# White.net
KiCad netlist of a schematic drawn in EAGLE
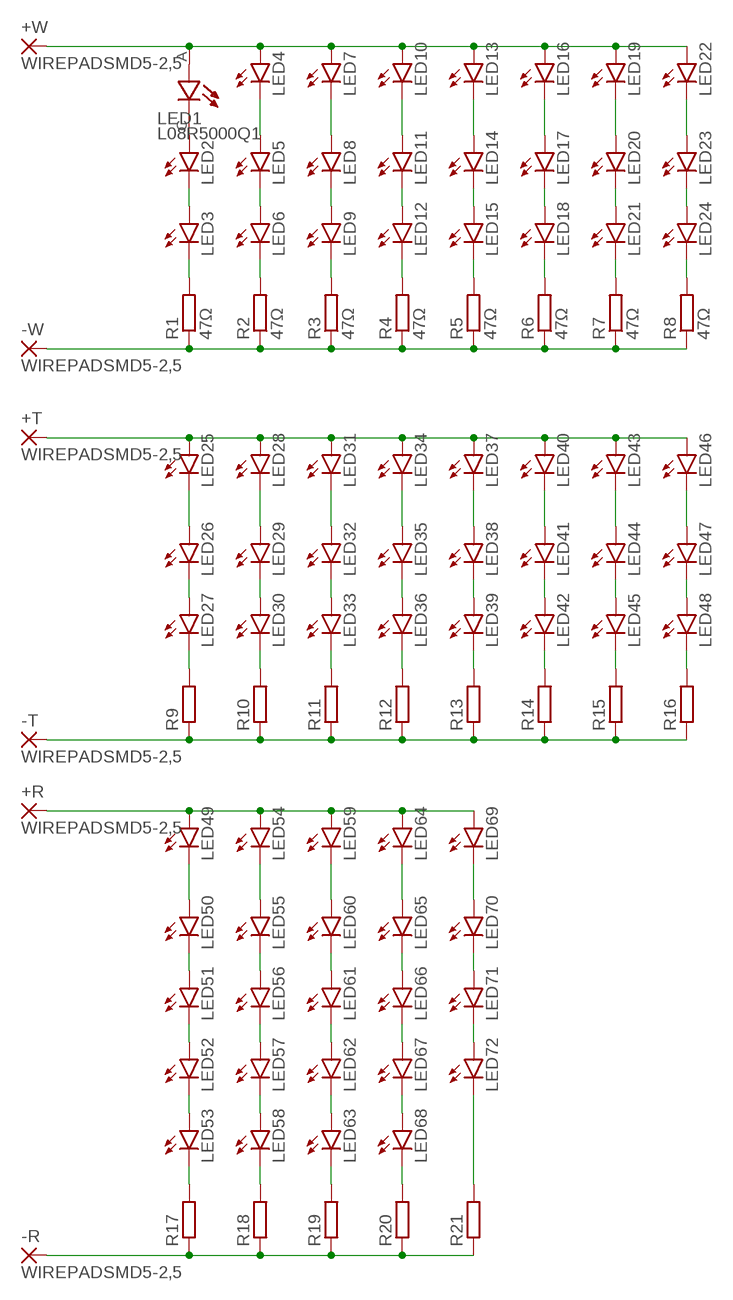
[diagram p0: schematic, sheet 1]

(export (version "E")
  (design (tool "Eeschema 10.0.6"))
  (components
    (comp (ref "+R")
      (value "WIREPADSMD5-2,5")
      (footprint "eagle-import:5-2,5")
      (libsource (lib "eagle-import") (part "WIREPADSMD5-2,5"))
    )
    (comp (ref "+T")
      (value "WIREPADSMD5-2,5")
      (footprint "eagle-import:5-2,5")
      (libsource (lib "eagle-import") (part "WIREPADSMD5-2,5"))
    )
    (comp (ref "+W")
      (value "WIREPADSMD5-2,5")
      (footprint "eagle-import:5-2,5")
      (libsource (lib "eagle-import") (part "WIREPADSMD5-2,5"))
    )
    (comp (ref "-R")
      (value "WIREPADSMD5-2,5")
      (footprint "eagle-import:5-2,5")
      (libsource (lib "eagle-import") (part "WIREPADSMD5-2,5"))
    )
    (comp (ref "-T")
      (value "WIREPADSMD5-2,5")
      (footprint "eagle-import:5-2,5")
      (libsource (lib "eagle-import") (part "WIREPADSMD5-2,5"))
    )
    (comp (ref "-W")
      (value "WIREPADSMD5-2,5")
      (footprint "eagle-import:5-2,5")
      (libsource (lib "eagle-import") (part "WIREPADSMD5-2,5"))
    )
    (comp (ref "LED1")
      (value "L08R5000Q1")
      (footprint "eagle-import:LEDRD254W57D500H1070")
      (fields (field (name "MF") "LED Technology"))
      (libsource (lib "eagle-import") (part "L08R5000Q1"))
    )
    (comp (ref "LED2")
      (value "LED5MM")
      (footprint "eagle-import:LED5MM")
      (libsource (lib "eagle-import") (part "LED5MM"))
    )
    (comp (ref "LED3")
      (value "LED5MM")
      (footprint "eagle-import:LED5MM")
      (libsource (lib "eagle-import") (part "LED5MM"))
    )
    (comp (ref "LED4")
      (value "LED5MM")
      (footprint "eagle-import:LED5MM")
      (libsource (lib "eagle-import") (part "LED5MM"))
    )
    (comp (ref "LED5")
      (value "LED5MM")
      (footprint "eagle-import:LED5MM")
      (libsource (lib "eagle-import") (part "LED5MM"))
    )
    (comp (ref "LED6")
      (value "LED5MM")
      (footprint "eagle-import:LED5MM")
      (libsource (lib "eagle-import") (part "LED5MM"))
    )
    (comp (ref "LED7")
      (value "LED5MM")
      (footprint "eagle-import:LED5MM")
      (libsource (lib "eagle-import") (part "LED5MM"))
    )
    (comp (ref "LED8")
      (value "LED5MM")
      (footprint "eagle-import:LED5MM")
      (libsource (lib "eagle-import") (part "LED5MM"))
    )
    (comp (ref "LED9")
      (value "LED5MM")
      (footprint "eagle-import:LED5MM")
      (libsource (lib "eagle-import") (part "LED5MM"))
    )
    (comp (ref "LED10")
      (value "LED5MM")
      (footprint "eagle-import:LED5MM")
      (libsource (lib "eagle-import") (part "LED5MM"))
    )
    (comp (ref "LED11")
      (value "LED5MM")
      (footprint "eagle-import:LED5MM")
      (libsource (lib "eagle-import") (part "LED5MM"))
    )
    (comp (ref "LED12")
      (value "LED5MM")
      (footprint "eagle-import:LED5MM")
      (libsource (lib "eagle-import") (part "LED5MM"))
    )
    (comp (ref "LED13")
      (value "LED5MM")
      (footprint "eagle-import:LED5MM")
      (libsource (lib "eagle-import") (part "LED5MM"))
    )
    (comp (ref "LED14")
      (value "LED5MM")
      (footprint "eagle-import:LED5MM")
      (libsource (lib "eagle-import") (part "LED5MM"))
    )
    (comp (ref "LED15")
      (value "LED5MM")
      (footprint "eagle-import:LED5MM")
      (libsource (lib "eagle-import") (part "LED5MM"))
    )
    (comp (ref "LED16")
      (value "LED5MM")
      (footprint "eagle-import:LED5MM")
      (libsource (lib "eagle-import") (part "LED5MM"))
    )
    (comp (ref "LED17")
      (value "LED5MM")
      (footprint "eagle-import:LED5MM")
      (libsource (lib "eagle-import") (part "LED5MM"))
    )
    (comp (ref "LED18")
      (value "LED5MM")
      (footprint "eagle-import:LED5MM")
      (libsource (lib "eagle-import") (part "LED5MM"))
    )
    (comp (ref "LED19")
      (value "LED5MM")
      (footprint "eagle-import:LED5MM")
      (libsource (lib "eagle-import") (part "LED5MM"))
    )
    (comp (ref "LED20")
      (value "LED5MM")
      (footprint "eagle-import:LED5MM")
      (libsource (lib "eagle-import") (part "LED5MM"))
    )
    (comp (ref "LED21")
      (value "LED5MM")
      (footprint "eagle-import:LED5MM")
      (libsource (lib "eagle-import") (part "LED5MM"))
    )
    (comp (ref "LED22")
      (value "LED5MM")
      (footprint "eagle-import:LED5MM")
      (libsource (lib "eagle-import") (part "LED5MM"))
    )
    (comp (ref "LED23")
      (value "LED5MM")
      (footprint "eagle-import:LED5MM")
      (libsource (lib "eagle-import") (part "LED5MM"))
    )
    (comp (ref "LED24")
      (value "LED5MM")
      (footprint "eagle-import:LED5MM")
      (libsource (lib "eagle-import") (part "LED5MM"))
    )
    (comp (ref "LED25")
      (value "LED5MM")
      (footprint "eagle-import:LED5MM")
      (libsource (lib "eagle-import") (part "LED5MM"))
    )
    (comp (ref "LED26")
      (value "LED5MM")
      (footprint "eagle-import:LED5MM")
      (libsource (lib "eagle-import") (part "LED5MM"))
    )
    (comp (ref "LED27")
      (value "LED5MM")
      (footprint "eagle-import:LED5MM")
      (libsource (lib "eagle-import") (part "LED5MM"))
    )
    (comp (ref "LED28")
      (value "LED5MM")
      (footprint "eagle-import:LED5MM")
      (libsource (lib "eagle-import") (part "LED5MM"))
    )
    (comp (ref "LED29")
      (value "LED5MM")
      (footprint "eagle-import:LED5MM")
      (libsource (lib "eagle-import") (part "LED5MM"))
    )
    (comp (ref "LED30")
      (value "LED5MM")
      (footprint "eagle-import:LED5MM")
      (libsource (lib "eagle-import") (part "LED5MM"))
    )
    (comp (ref "LED31")
      (value "LED5MM")
      (footprint "eagle-import:LED5MM")
      (libsource (lib "eagle-import") (part "LED5MM"))
    )
    (comp (ref "LED32")
      (value "LED5MM")
      (footprint "eagle-import:LED5MM")
      (libsource (lib "eagle-import") (part "LED5MM"))
    )
    (comp (ref "LED33")
      (value "LED5MM")
      (footprint "eagle-import:LED5MM")
      (libsource (lib "eagle-import") (part "LED5MM"))
    )
    (comp (ref "LED34")
      (value "LED5MM")
      (footprint "eagle-import:LED5MM")
      (libsource (lib "eagle-import") (part "LED5MM"))
    )
    (comp (ref "LED35")
      (value "LED5MM")
      (footprint "eagle-import:LED5MM")
      (libsource (lib "eagle-import") (part "LED5MM"))
    )
    (comp (ref "LED36")
      (value "LED5MM")
      (footprint "eagle-import:LED5MM")
      (libsource (lib "eagle-import") (part "LED5MM"))
    )
    (comp (ref "LED37")
      (value "LED5MM")
      (footprint "eagle-import:LED5MM")
      (libsource (lib "eagle-import") (part "LED5MM"))
    )
    (comp (ref "LED38")
      (value "LED5MM")
      (footprint "eagle-import:LED5MM")
      (libsource (lib "eagle-import") (part "LED5MM"))
    )
    (comp (ref "LED39")
      (value "LED5MM")
      (footprint "eagle-import:LED5MM")
      (libsource (lib "eagle-import") (part "LED5MM"))
    )
    (comp (ref "LED40")
      (value "LED5MM")
      (footprint "eagle-import:LED5MM")
      (libsource (lib "eagle-import") (part "LED5MM"))
    )
    (comp (ref "LED41")
      (value "LED5MM")
      (footprint "eagle-import:LED5MM")
      (libsource (lib "eagle-import") (part "LED5MM"))
    )
    (comp (ref "LED42")
      (value "LED5MM")
      (footprint "eagle-import:LED5MM")
      (libsource (lib "eagle-import") (part "LED5MM"))
    )
    (comp (ref "LED43")
      (value "LED5MM")
      (footprint "eagle-import:LED5MM")
      (libsource (lib "eagle-import") (part "LED5MM"))
    )
    (comp (ref "LED44")
      (value "LED5MM")
      (footprint "eagle-import:LED5MM")
      (libsource (lib "eagle-import") (part "LED5MM"))
    )
    (comp (ref "LED45")
      (value "LED5MM")
      (footprint "eagle-import:LED5MM")
      (libsource (lib "eagle-import") (part "LED5MM"))
    )
    (comp (ref "LED46")
      (value "LED5MM")
      (footprint "eagle-import:LED5MM")
      (libsource (lib "eagle-import") (part "LED5MM"))
    )
    (comp (ref "LED47")
      (value "LED5MM")
      (footprint "eagle-import:LED5MM")
      (libsource (lib "eagle-import") (part "LED5MM"))
    )
    (comp (ref "LED48")
      (value "LED5MM")
      (footprint "eagle-import:LED5MM")
      (libsource (lib "eagle-import") (part "LED5MM"))
    )
    (comp (ref "LED49")
      (value "LED5MM")
      (footprint "eagle-import:LED5MM")
      (libsource (lib "eagle-import") (part "LED5MM"))
    )
    (comp (ref "LED50")
      (value "LED5MM")
      (footprint "eagle-import:LED5MM")
      (libsource (lib "eagle-import") (part "LED5MM"))
    )
    (comp (ref "LED51")
      (value "LED5MM")
      (footprint "eagle-import:LED5MM")
      (libsource (lib "eagle-import") (part "LED5MM"))
    )
    (comp (ref "LED52")
      (value "LED5MM")
      (footprint "eagle-import:LED5MM")
      (libsource (lib "eagle-import") (part "LED5MM"))
    )
    (comp (ref "LED53")
      (value "LED5MM")
      (footprint "eagle-import:LED5MM")
      (libsource (lib "eagle-import") (part "LED5MM"))
    )
    (comp (ref "LED54")
      (value "LED5MM")
      (footprint "eagle-import:LED5MM")
      (libsource (lib "eagle-import") (part "LED5MM"))
    )
    (comp (ref "LED55")
      (value "LED5MM")
      (footprint "eagle-import:LED5MM")
      (libsource (lib "eagle-import") (part "LED5MM"))
    )
    (comp (ref "LED56")
      (value "LED5MM")
      (footprint "eagle-import:LED5MM")
      (libsource (lib "eagle-import") (part "LED5MM"))
    )
    (comp (ref "LED57")
      (value "LED5MM")
      (footprint "eagle-import:LED5MM")
      (libsource (lib "eagle-import") (part "LED5MM"))
    )
    (comp (ref "LED58")
      (value "LED5MM")
      (footprint "eagle-import:LED5MM")
      (libsource (lib "eagle-import") (part "LED5MM"))
    )
    (comp (ref "LED59")
      (value "LED5MM")
      (footprint "eagle-import:LED5MM")
      (libsource (lib "eagle-import") (part "LED5MM"))
    )
    (comp (ref "LED60")
      (value "LED5MM")
      (footprint "eagle-import:LED5MM")
      (libsource (lib "eagle-import") (part "LED5MM"))
    )
    (comp (ref "LED61")
      (value "LED5MM")
      (footprint "eagle-import:LED5MM")
      (libsource (lib "eagle-import") (part "LED5MM"))
    )
    (comp (ref "LED62")
      (value "LED5MM")
      (footprint "eagle-import:LED5MM")
      (libsource (lib "eagle-import") (part "LED5MM"))
    )
    (comp (ref "LED63")
      (value "LED5MM")
      (footprint "eagle-import:LED5MM")
      (libsource (lib "eagle-import") (part "LED5MM"))
    )
    (comp (ref "LED64")
      (value "LED5MM")
      (footprint "eagle-import:LED5MM")
      (libsource (lib "eagle-import") (part "LED5MM"))
    )
    (comp (ref "LED65")
      (value "LED5MM")
      (footprint "eagle-import:LED5MM")
      (libsource (lib "eagle-import") (part "LED5MM"))
    )
    (comp (ref "LED66")
      (value "LED5MM")
      (footprint "eagle-import:LED5MM")
      (libsource (lib "eagle-import") (part "LED5MM"))
    )
    (comp (ref "LED67")
      (value "LED5MM")
      (footprint "eagle-import:LED5MM")
      (libsource (lib "eagle-import") (part "LED5MM"))
    )
    (comp (ref "LED68")
      (value "LED5MM")
      (footprint "eagle-import:LED5MM")
      (libsource (lib "eagle-import") (part "LED5MM"))
    )
    (comp (ref "LED69")
      (value "LED5MM")
      (footprint "eagle-import:LED5MM")
      (libsource (lib "eagle-import") (part "LED5MM"))
    )
    (comp (ref "LED70")
      (value "LED5MM")
      (footprint "eagle-import:LED5MM")
      (libsource (lib "eagle-import") (part "LED5MM"))
    )
    (comp (ref "LED71")
      (value "LED5MM")
      (footprint "eagle-import:LED5MM")
      (libsource (lib "eagle-import") (part "LED5MM"))
    )
    (comp (ref "LED72")
      (value "LED5MM")
      (footprint "eagle-import:LED5MM")
      (libsource (lib "eagle-import") (part "LED5MM"))
    )
    (comp (ref "R1")
      (value "47Ω")
      (footprint "eagle-import:0411_15")
      (libsource (lib "eagle-import") (part "R-EU_0411/15"))
    )
    (comp (ref "R2")
      (value "47Ω")
      (footprint "eagle-import:0411_15")
      (libsource (lib "eagle-import") (part "R-EU_0411/15"))
    )
    (comp (ref "R3")
      (value "47Ω")
      (footprint "eagle-import:0411_15")
      (libsource (lib "eagle-import") (part "R-EU_0411/15"))
    )
    (comp (ref "R4")
      (value "47Ω")
      (footprint "eagle-import:0411_15")
      (libsource (lib "eagle-import") (part "R-EU_0411/15"))
    )
    (comp (ref "R5")
      (value "47Ω")
      (footprint "eagle-import:0411_15")
      (libsource (lib "eagle-import") (part "R-EU_0411/15"))
    )
    (comp (ref "R6")
      (value "47Ω")
      (footprint "eagle-import:0411_15")
      (libsource (lib "eagle-import") (part "R-EU_0411/15"))
    )
    (comp (ref "R7")
      (value "47Ω")
      (footprint "eagle-import:0411_15")
      (libsource (lib "eagle-import") (part "R-EU_0411/15"))
    )
    (comp (ref "R8")
      (value "47Ω")
      (footprint "eagle-import:0411_15")
      (libsource (lib "eagle-import") (part "R-EU_0411/15"))
    )
    (comp (ref "R9")
      (value "R-EU_0207/12")
      (footprint "eagle-import:0207_12")
      (libsource (lib "eagle-import") (part "R-EU_0207/12"))
    )
    (comp (ref "R10")
      (value "R-EU_0207/12")
      (footprint "eagle-import:0207_12")
      (libsource (lib "eagle-import") (part "R-EU_0207/12"))
    )
    (comp (ref "R11")
      (value "R-EU_0207/12")
      (footprint "eagle-import:0207_12")
      (libsource (lib "eagle-import") (part "R-EU_0207/12"))
    )
    (comp (ref "R12")
      (value "R-EU_0207/12")
      (footprint "eagle-import:0207_12")
      (libsource (lib "eagle-import") (part "R-EU_0207/12"))
    )
    (comp (ref "R13")
      (value "R-EU_0207/12")
      (footprint "eagle-import:0207_12")
      (libsource (lib "eagle-import") (part "R-EU_0207/12"))
    )
    (comp (ref "R14")
      (value "R-EU_0207/12")
      (footprint "eagle-import:0207_12")
      (libsource (lib "eagle-import") (part "R-EU_0207/12"))
    )
    (comp (ref "R15")
      (value "R-EU_0207/12")
      (footprint "eagle-import:0207_12")
      (libsource (lib "eagle-import") (part "R-EU_0207/12"))
    )
    (comp (ref "R16")
      (value "R-EU_0207/12")
      (footprint "eagle-import:0207_12")
      (libsource (lib "eagle-import") (part "R-EU_0207/12"))
    )
    (comp (ref "R17")
      (value "R-EU_0207/12")
      (footprint "eagle-import:0207_12")
      (libsource (lib "eagle-import") (part "R-EU_0207/12"))
    )
    (comp (ref "R18")
      (value "R-EU_0207/12")
      (footprint "eagle-import:0207_12")
      (libsource (lib "eagle-import") (part "R-EU_0207/12"))
    )
    (comp (ref "R19")
      (value "R-EU_0207/12")
      (footprint "eagle-import:0207_12")
      (libsource (lib "eagle-import") (part "R-EU_0207/12"))
    )
    (comp (ref "R20")
      (value "R-EU_0207/12")
      (footprint "eagle-import:0207_12")
      (libsource (lib "eagle-import") (part "R-EU_0207/12"))
    )
    (comp (ref "R21")
      (value "R-EU_0207/12")
      (footprint "eagle-import:0207_12")
      (libsource (lib "eagle-import") (part "R-EU_0207/12"))
    )
  )
  (nets
    (net (code "1") (name "Net-(+R-P)") (class "Default")
      (node (ref "+R") (pin "1") (pinfunction "P_1") (pintype "passive"))
      (node (ref "LED49") (pin "A") (pinfunction "A_A") (pintype "passive"))
      (node (ref "LED54") (pin "A") (pinfunction "A_A") (pintype "passive"))
      (node (ref "LED59") (pin "A") (pinfunction "A_A") (pintype "passive"))
      (node (ref "LED64") (pin "A") (pinfunction "A_A") (pintype "passive"))
      (node (ref "LED69") (pin "A") (pinfunction "A_A") (pintype "passive"))
    )
    (net (code "2") (name "Net-(+T-P)") (class "Default")
      (node (ref "+T") (pin "1") (pinfunction "P_1") (pintype "passive"))
      (node (ref "LED25") (pin "A") (pinfunction "A_A") (pintype "passive"))
      (node (ref "LED28") (pin "A") (pinfunction "A_A") (pintype "passive"))
      (node (ref "LED31") (pin "A") (pinfunction "A_A") (pintype "passive"))
      (node (ref "LED34") (pin "A") (pinfunction "A_A") (pintype "passive"))
      (node (ref "LED37") (pin "A") (pinfunction "A_A") (pintype "passive"))
      (node (ref "LED40") (pin "A") (pinfunction "A_A") (pintype "passive"))
      (node (ref "LED43") (pin "A") (pinfunction "A_A") (pintype "passive"))
      (node (ref "LED46") (pin "A") (pinfunction "A_A") (pintype "passive"))
    )
    (net (code "3") (name "Net-(+W-P)") (class "Default")
      (node (ref "+W") (pin "1") (pinfunction "P_1") (pintype "passive"))
      (node (ref "LED1") (pin "A") (pinfunction "A_A") (pintype "passive"))
      (node (ref "LED10") (pin "A") (pinfunction "A_A") (pintype "passive"))
      (node (ref "LED13") (pin "A") (pinfunction "A_A") (pintype "passive"))
      (node (ref "LED16") (pin "A") (pinfunction "A_A") (pintype "passive"))
      (node (ref "LED19") (pin "A") (pinfunction "A_A") (pintype "passive"))
      (node (ref "LED22") (pin "A") (pinfunction "A_A") (pintype "passive"))
      (node (ref "LED4") (pin "A") (pinfunction "A_A") (pintype "passive"))
      (node (ref "LED7") (pin "A") (pinfunction "A_A") (pintype "passive"))
    )
    (net (code "4") (name "Net-(-R-P)") (class "Default")
      (node (ref "-R") (pin "1") (pinfunction "P_1") (pintype "passive"))
      (node (ref "R17") (pin "1") (pinfunction "1_1") (pintype "passive"))
      (node (ref "R18") (pin "1") (pinfunction "1_1") (pintype "passive"))
      (node (ref "R19") (pin "1") (pinfunction "1_1") (pintype "passive"))
      (node (ref "R20") (pin "1") (pinfunction "1_1") (pintype "passive"))
      (node (ref "R21") (pin "1") (pinfunction "1_1") (pintype "passive"))
    )
    (net (code "5") (name "Net-(-T-P)") (class "Default")
      (node (ref "-T") (pin "1") (pinfunction "P_1") (pintype "passive"))
      (node (ref "R10") (pin "1") (pinfunction "1_1") (pintype "passive"))
      (node (ref "R11") (pin "1") (pinfunction "1_1") (pintype "passive"))
      (node (ref "R12") (pin "1") (pinfunction "1_1") (pintype "passive"))
      (node (ref "R13") (pin "1") (pinfunction "1_1") (pintype "passive"))
      (node (ref "R14") (pin "1") (pinfunction "1_1") (pintype "passive"))
      (node (ref "R15") (pin "1") (pinfunction "1_1") (pintype "passive"))
      (node (ref "R16") (pin "1") (pinfunction "1_1") (pintype "passive"))
      (node (ref "R9") (pin "1") (pinfunction "1_1") (pintype "passive"))
    )
    (net (code "6") (name "Net-(-W-P)") (class "Default")
      (node (ref "-W") (pin "1") (pinfunction "P_1") (pintype "passive"))
      (node (ref "R1") (pin "1") (pinfunction "1_1") (pintype "passive"))
      (node (ref "R2") (pin "1") (pinfunction "1_1") (pintype "passive"))
      (node (ref "R3") (pin "1") (pinfunction "1_1") (pintype "passive"))
      (node (ref "R4") (pin "1") (pinfunction "1_1") (pintype "passive"))
      (node (ref "R5") (pin "1") (pinfunction "1_1") (pintype "passive"))
      (node (ref "R6") (pin "1") (pinfunction "1_1") (pintype "passive"))
      (node (ref "R7") (pin "1") (pinfunction "1_1") (pintype "passive"))
      (node (ref "R8") (pin "1") (pinfunction "1_1") (pintype "passive"))
    )
    (net (code "7") (name "Net-(LED1-PadC)") (class "Default")
      (node (ref "LED1") (pin "C") (pinfunction "C_C") (pintype "passive"))
      (node (ref "LED2") (pin "A") (pinfunction "A_A") (pintype "passive"))
    )
    (net (code "8") (name "Net-(LED2-C)") (class "Default")
      (node (ref "LED2") (pin "K") (pinfunction "C_K") (pintype "passive"))
      (node (ref "LED3") (pin "A") (pinfunction "A_A") (pintype "passive"))
    )
    (net (code "9") (name "Net-(LED3-C)") (class "Default")
      (node (ref "LED3") (pin "K") (pinfunction "C_K") (pintype "passive"))
      (node (ref "R1") (pin "2") (pinfunction "2_2") (pintype "passive"))
    )
    (net (code "10") (name "Net-(LED4-C)") (class "Default")
      (node (ref "LED4") (pin "K") (pinfunction "C_K") (pintype "passive"))
      (node (ref "LED5") (pin "A") (pinfunction "A_A") (pintype "passive"))
    )
    (net (code "11") (name "Net-(LED5-C)") (class "Default")
      (node (ref "LED5") (pin "K") (pinfunction "C_K") (pintype "passive"))
      (node (ref "LED6") (pin "A") (pinfunction "A_A") (pintype "passive"))
    )
    (net (code "12") (name "Net-(LED6-C)") (class "Default")
      (node (ref "LED6") (pin "K") (pinfunction "C_K") (pintype "passive"))
      (node (ref "R2") (pin "2") (pinfunction "2_2") (pintype "passive"))
    )
    (net (code "13") (name "Net-(LED7-C)") (class "Default")
      (node (ref "LED7") (pin "K") (pinfunction "C_K") (pintype "passive"))
      (node (ref "LED8") (pin "A") (pinfunction "A_A") (pintype "passive"))
    )
    (net (code "14") (name "Net-(LED8-C)") (class "Default")
      (node (ref "LED8") (pin "K") (pinfunction "C_K") (pintype "passive"))
      (node (ref "LED9") (pin "A") (pinfunction "A_A") (pintype "passive"))
    )
    (net (code "15") (name "Net-(LED9-C)") (class "Default")
      (node (ref "LED9") (pin "K") (pinfunction "C_K") (pintype "passive"))
      (node (ref "R3") (pin "2") (pinfunction "2_2") (pintype "passive"))
    )
    (net (code "16") (name "Net-(LED10-C)") (class "Default")
      (node (ref "LED10") (pin "K") (pinfunction "C_K") (pintype "passive"))
      (node (ref "LED11") (pin "A") (pinfunction "A_A") (pintype "passive"))
    )
    (net (code "17") (name "Net-(LED11-C)") (class "Default")
      (node (ref "LED11") (pin "K") (pinfunction "C_K") (pintype "passive"))
      (node (ref "LED12") (pin "A") (pinfunction "A_A") (pintype "passive"))
    )
    (net (code "18") (name "Net-(LED12-C)") (class "Default")
      (node (ref "LED12") (pin "K") (pinfunction "C_K") (pintype "passive"))
      (node (ref "R4") (pin "2") (pinfunction "2_2") (pintype "passive"))
    )
    (net (code "19") (name "Net-(LED13-C)") (class "Default")
      (node (ref "LED13") (pin "K") (pinfunction "C_K") (pintype "passive"))
      (node (ref "LED14") (pin "A") (pinfunction "A_A") (pintype "passive"))
    )
    (net (code "20") (name "Net-(LED14-C)") (class "Default")
      (node (ref "LED14") (pin "K") (pinfunction "C_K") (pintype "passive"))
      (node (ref "LED15") (pin "A") (pinfunction "A_A") (pintype "passive"))
    )
    (net (code "21") (name "Net-(LED15-C)") (class "Default")
      (node (ref "LED15") (pin "K") (pinfunction "C_K") (pintype "passive"))
      (node (ref "R5") (pin "2") (pinfunction "2_2") (pintype "passive"))
    )
    (net (code "22") (name "Net-(LED16-C)") (class "Default")
      (node (ref "LED16") (pin "K") (pinfunction "C_K") (pintype "passive"))
      (node (ref "LED17") (pin "A") (pinfunction "A_A") (pintype "passive"))
    )
    (net (code "23") (name "Net-(LED17-C)") (class "Default")
      (node (ref "LED17") (pin "K") (pinfunction "C_K") (pintype "passive"))
      (node (ref "LED18") (pin "A") (pinfunction "A_A") (pintype "passive"))
    )
    (net (code "24") (name "Net-(LED18-C)") (class "Default")
      (node (ref "LED18") (pin "K") (pinfunction "C_K") (pintype "passive"))
      (node (ref "R6") (pin "2") (pinfunction "2_2") (pintype "passive"))
    )
    (net (code "25") (name "Net-(LED19-C)") (class "Default")
      (node (ref "LED19") (pin "K") (pinfunction "C_K") (pintype "passive"))
      (node (ref "LED20") (pin "A") (pinfunction "A_A") (pintype "passive"))
    )
    (net (code "26") (name "Net-(LED20-C)") (class "Default")
      (node (ref "LED20") (pin "K") (pinfunction "C_K") (pintype "passive"))
      (node (ref "LED21") (pin "A") (pinfunction "A_A") (pintype "passive"))
    )
    (net (code "27") (name "Net-(LED21-C)") (class "Default")
      (node (ref "LED21") (pin "K") (pinfunction "C_K") (pintype "passive"))
      (node (ref "R7") (pin "2") (pinfunction "2_2") (pintype "passive"))
    )
    (net (code "28") (name "Net-(LED22-C)") (class "Default")
      (node (ref "LED22") (pin "K") (pinfunction "C_K") (pintype "passive"))
      (node (ref "LED23") (pin "A") (pinfunction "A_A") (pintype "passive"))
    )
    (net (code "29") (name "Net-(LED23-C)") (class "Default")
      (node (ref "LED23") (pin "K") (pinfunction "C_K") (pintype "passive"))
      (node (ref "LED24") (pin "A") (pinfunction "A_A") (pintype "passive"))
    )
    (net (code "30") (name "Net-(LED24-C)") (class "Default")
      (node (ref "LED24") (pin "K") (pinfunction "C_K") (pintype "passive"))
      (node (ref "R8") (pin "2") (pinfunction "2_2") (pintype "passive"))
    )
    (net (code "31") (name "Net-(LED25-C)") (class "Default")
      (node (ref "LED25") (pin "K") (pinfunction "C_K") (pintype "passive"))
      (node (ref "LED26") (pin "A") (pinfunction "A_A") (pintype "passive"))
    )
    (net (code "32") (name "Net-(LED26-C)") (class "Default")
      (node (ref "LED26") (pin "K") (pinfunction "C_K") (pintype "passive"))
      (node (ref "LED27") (pin "A") (pinfunction "A_A") (pintype "passive"))
    )
    (net (code "33") (name "Net-(LED27-C)") (class "Default")
      (node (ref "LED27") (pin "K") (pinfunction "C_K") (pintype "passive"))
      (node (ref "R9") (pin "2") (pinfunction "2_2") (pintype "passive"))
    )
    (net (code "34") (name "Net-(LED28-C)") (class "Default")
      (node (ref "LED28") (pin "K") (pinfunction "C_K") (pintype "passive"))
      (node (ref "LED29") (pin "A") (pinfunction "A_A") (pintype "passive"))
    )
    (net (code "35") (name "Net-(LED29-C)") (class "Default")
      (node (ref "LED29") (pin "K") (pinfunction "C_K") (pintype "passive"))
      (node (ref "LED30") (pin "A") (pinfunction "A_A") (pintype "passive"))
    )
    (net (code "36") (name "Net-(LED30-C)") (class "Default")
      (node (ref "LED30") (pin "K") (pinfunction "C_K") (pintype "passive"))
      (node (ref "R10") (pin "2") (pinfunction "2_2") (pintype "passive"))
    )
    (net (code "37") (name "Net-(LED31-C)") (class "Default")
      (node (ref "LED31") (pin "K") (pinfunction "C_K") (pintype "passive"))
      (node (ref "LED32") (pin "A") (pinfunction "A_A") (pintype "passive"))
    )
    (net (code "38") (name "Net-(LED32-C)") (class "Default")
      (node (ref "LED32") (pin "K") (pinfunction "C_K") (pintype "passive"))
      (node (ref "LED33") (pin "A") (pinfunction "A_A") (pintype "passive"))
    )
    (net (code "39") (name "Net-(LED33-C)") (class "Default")
      (node (ref "LED33") (pin "K") (pinfunction "C_K") (pintype "passive"))
      (node (ref "R11") (pin "2") (pinfunction "2_2") (pintype "passive"))
    )
    (net (code "40") (name "Net-(LED34-C)") (class "Default")
      (node (ref "LED34") (pin "K") (pinfunction "C_K") (pintype "passive"))
      (node (ref "LED35") (pin "A") (pinfunction "A_A") (pintype "passive"))
    )
    (net (code "41") (name "Net-(LED35-C)") (class "Default")
      (node (ref "LED35") (pin "K") (pinfunction "C_K") (pintype "passive"))
      (node (ref "LED36") (pin "A") (pinfunction "A_A") (pintype "passive"))
    )
    (net (code "42") (name "Net-(LED36-C)") (class "Default")
      (node (ref "LED36") (pin "K") (pinfunction "C_K") (pintype "passive"))
      (node (ref "R12") (pin "2") (pinfunction "2_2") (pintype "passive"))
    )
    (net (code "43") (name "Net-(LED37-C)") (class "Default")
      (node (ref "LED37") (pin "K") (pinfunction "C_K") (pintype "passive"))
      (node (ref "LED38") (pin "A") (pinfunction "A_A") (pintype "passive"))
    )
    (net (code "44") (name "Net-(LED38-C)") (class "Default")
      (node (ref "LED38") (pin "K") (pinfunction "C_K") (pintype "passive"))
      (node (ref "LED39") (pin "A") (pinfunction "A_A") (pintype "passive"))
    )
    (net (code "45") (name "Net-(LED39-C)") (class "Default")
      (node (ref "LED39") (pin "K") (pinfunction "C_K") (pintype "passive"))
      (node (ref "R13") (pin "2") (pinfunction "2_2") (pintype "passive"))
    )
    (net (code "46") (name "Net-(LED40-C)") (class "Default")
      (node (ref "LED40") (pin "K") (pinfunction "C_K") (pintype "passive"))
      (node (ref "LED41") (pin "A") (pinfunction "A_A") (pintype "passive"))
    )
    (net (code "47") (name "Net-(LED41-C)") (class "Default")
      (node (ref "LED41") (pin "K") (pinfunction "C_K") (pintype "passive"))
      (node (ref "LED42") (pin "A") (pinfunction "A_A") (pintype "passive"))
    )
    (net (code "48") (name "Net-(LED42-C)") (class "Default")
      (node (ref "LED42") (pin "K") (pinfunction "C_K") (pintype "passive"))
      (node (ref "R14") (pin "2") (pinfunction "2_2") (pintype "passive"))
    )
    (net (code "49") (name "Net-(LED43-C)") (class "Default")
      (node (ref "LED43") (pin "K") (pinfunction "C_K") (pintype "passive"))
      (node (ref "LED44") (pin "A") (pinfunction "A_A") (pintype "passive"))
    )
    (net (code "50") (name "Net-(LED44-C)") (class "Default")
      (node (ref "LED44") (pin "K") (pinfunction "C_K") (pintype "passive"))
      (node (ref "LED45") (pin "A") (pinfunction "A_A") (pintype "passive"))
    )
    (net (code "51") (name "Net-(LED45-C)") (class "Default")
      (node (ref "LED45") (pin "K") (pinfunction "C_K") (pintype "passive"))
      (node (ref "R15") (pin "2") (pinfunction "2_2") (pintype "passive"))
    )
    (net (code "52") (name "Net-(LED46-C)") (class "Default")
      (node (ref "LED46") (pin "K") (pinfunction "C_K") (pintype "passive"))
      (node (ref "LED47") (pin "A") (pinfunction "A_A") (pintype "passive"))
    )
    (net (code "53") (name "Net-(LED47-C)") (class "Default")
      (node (ref "LED47") (pin "K") (pinfunction "C_K") (pintype "passive"))
      (node (ref "LED48") (pin "A") (pinfunction "A_A") (pintype "passive"))
    )
    (net (code "54") (name "Net-(LED48-C)") (class "Default")
      (node (ref "LED48") (pin "K") (pinfunction "C_K") (pintype "passive"))
      (node (ref "R16") (pin "2") (pinfunction "2_2") (pintype "passive"))
    )
    (net (code "55") (name "Net-(LED49-C)") (class "Default")
      (node (ref "LED49") (pin "K") (pinfunction "C_K") (pintype "passive"))
      (node (ref "LED50") (pin "A") (pinfunction "A_A") (pintype "passive"))
    )
    (net (code "56") (name "Net-(LED50-C)") (class "Default")
      (node (ref "LED50") (pin "K") (pinfunction "C_K") (pintype "passive"))
      (node (ref "LED51") (pin "A") (pinfunction "A_A") (pintype "passive"))
    )
    (net (code "57") (name "Net-(LED51-C)") (class "Default")
      (node (ref "LED51") (pin "K") (pinfunction "C_K") (pintype "passive"))
      (node (ref "LED52") (pin "A") (pinfunction "A_A") (pintype "passive"))
    )
    (net (code "58") (name "Net-(LED52-C)") (class "Default")
      (node (ref "LED52") (pin "K") (pinfunction "C_K") (pintype "passive"))
      (node (ref "LED53") (pin "A") (pinfunction "A_A") (pintype "passive"))
    )
    (net (code "59") (name "Net-(LED53-C)") (class "Default")
      (node (ref "LED53") (pin "K") (pinfunction "C_K") (pintype "passive"))
      (node (ref "R17") (pin "2") (pinfunction "2_2") (pintype "passive"))
    )
    (net (code "60") (name "Net-(LED54-C)") (class "Default")
      (node (ref "LED54") (pin "K") (pinfunction "C_K") (pintype "passive"))
      (node (ref "LED55") (pin "A") (pinfunction "A_A") (pintype "passive"))
    )
    (net (code "61") (name "Net-(LED55-C)") (class "Default")
      (node (ref "LED55") (pin "K") (pinfunction "C_K") (pintype "passive"))
      (node (ref "LED56") (pin "A") (pinfunction "A_A") (pintype "passive"))
    )
    (net (code "62") (name "Net-(LED56-C)") (class "Default")
      (node (ref "LED56") (pin "K") (pinfunction "C_K") (pintype "passive"))
      (node (ref "LED57") (pin "A") (pinfunction "A_A") (pintype "passive"))
    )
    (net (code "63") (name "Net-(LED57-C)") (class "Default")
      (node (ref "LED57") (pin "K") (pinfunction "C_K") (pintype "passive"))
      (node (ref "LED58") (pin "A") (pinfunction "A_A") (pintype "passive"))
    )
    (net (code "64") (name "Net-(LED58-C)") (class "Default")
      (node (ref "LED58") (pin "K") (pinfunction "C_K") (pintype "passive"))
      (node (ref "R18") (pin "2") (pinfunction "2_2") (pintype "passive"))
    )
    (net (code "65") (name "Net-(LED59-C)") (class "Default")
      (node (ref "LED59") (pin "K") (pinfunction "C_K") (pintype "passive"))
      (node (ref "LED60") (pin "A") (pinfunction "A_A") (pintype "passive"))
    )
    (net (code "66") (name "Net-(LED60-C)") (class "Default")
      (node (ref "LED60") (pin "K") (pinfunction "C_K") (pintype "passive"))
      (node (ref "LED61") (pin "A") (pinfunction "A_A") (pintype "passive"))
    )
    (net (code "67") (name "Net-(LED61-C)") (class "Default")
      (node (ref "LED61") (pin "K") (pinfunction "C_K") (pintype "passive"))
      (node (ref "LED62") (pin "A") (pinfunction "A_A") (pintype "passive"))
    )
    (net (code "68") (name "Net-(LED62-C)") (class "Default")
      (node (ref "LED62") (pin "K") (pinfunction "C_K") (pintype "passive"))
      (node (ref "LED63") (pin "A") (pinfunction "A_A") (pintype "passive"))
    )
    (net (code "69") (name "Net-(LED63-C)") (class "Default")
      (node (ref "LED63") (pin "K") (pinfunction "C_K") (pintype "passive"))
      (node (ref "R19") (pin "2") (pinfunction "2_2") (pintype "passive"))
    )
    (net (code "70") (name "Net-(LED64-C)") (class "Default")
      (node (ref "LED64") (pin "K") (pinfunction "C_K") (pintype "passive"))
      (node (ref "LED65") (pin "A") (pinfunction "A_A") (pintype "passive"))
    )
    (net (code "71") (name "Net-(LED65-C)") (class "Default")
      (node (ref "LED65") (pin "K") (pinfunction "C_K") (pintype "passive"))
      (node (ref "LED66") (pin "A") (pinfunction "A_A") (pintype "passive"))
    )
    (net (code "72") (name "Net-(LED66-C)") (class "Default")
      (node (ref "LED66") (pin "K") (pinfunction "C_K") (pintype "passive"))
      (node (ref "LED67") (pin "A") (pinfunction "A_A") (pintype "passive"))
    )
    (net (code "73") (name "Net-(LED67-C)") (class "Default")
      (node (ref "LED67") (pin "K") (pinfunction "C_K") (pintype "passive"))
      (node (ref "LED68") (pin "A") (pinfunction "A_A") (pintype "passive"))
    )
    (net (code "74") (name "Net-(LED68-C)") (class "Default")
      (node (ref "LED68") (pin "K") (pinfunction "C_K") (pintype "passive"))
      (node (ref "R20") (pin "2") (pinfunction "2_2") (pintype "passive"))
    )
    (net (code "75") (name "Net-(LED69-C)") (class "Default")
      (node (ref "LED69") (pin "K") (pinfunction "C_K") (pintype "passive"))
      (node (ref "LED70") (pin "A") (pinfunction "A_A") (pintype "passive"))
    )
    (net (code "76") (name "Net-(LED70-C)") (class "Default")
      (node (ref "LED70") (pin "K") (pinfunction "C_K") (pintype "passive"))
      (node (ref "LED71") (pin "A") (pinfunction "A_A") (pintype "passive"))
    )
    (net (code "77") (name "Net-(LED71-C)") (class "Default")
      (node (ref "LED71") (pin "K") (pinfunction "C_K") (pintype "passive"))
      (node (ref "LED72") (pin "A") (pinfunction "A_A") (pintype "passive"))
    )
    (net (code "78") (name "Net-(LED72-C)") (class "Default")
      (node (ref "LED72") (pin "K") (pinfunction "C_K") (pintype "passive"))
      (node (ref "R21") (pin "2") (pinfunction "2_2") (pintype "passive"))
    )
  )
)
